# Laser_Charger.net
KiCad netlist of a schematic drawn in EAGLE
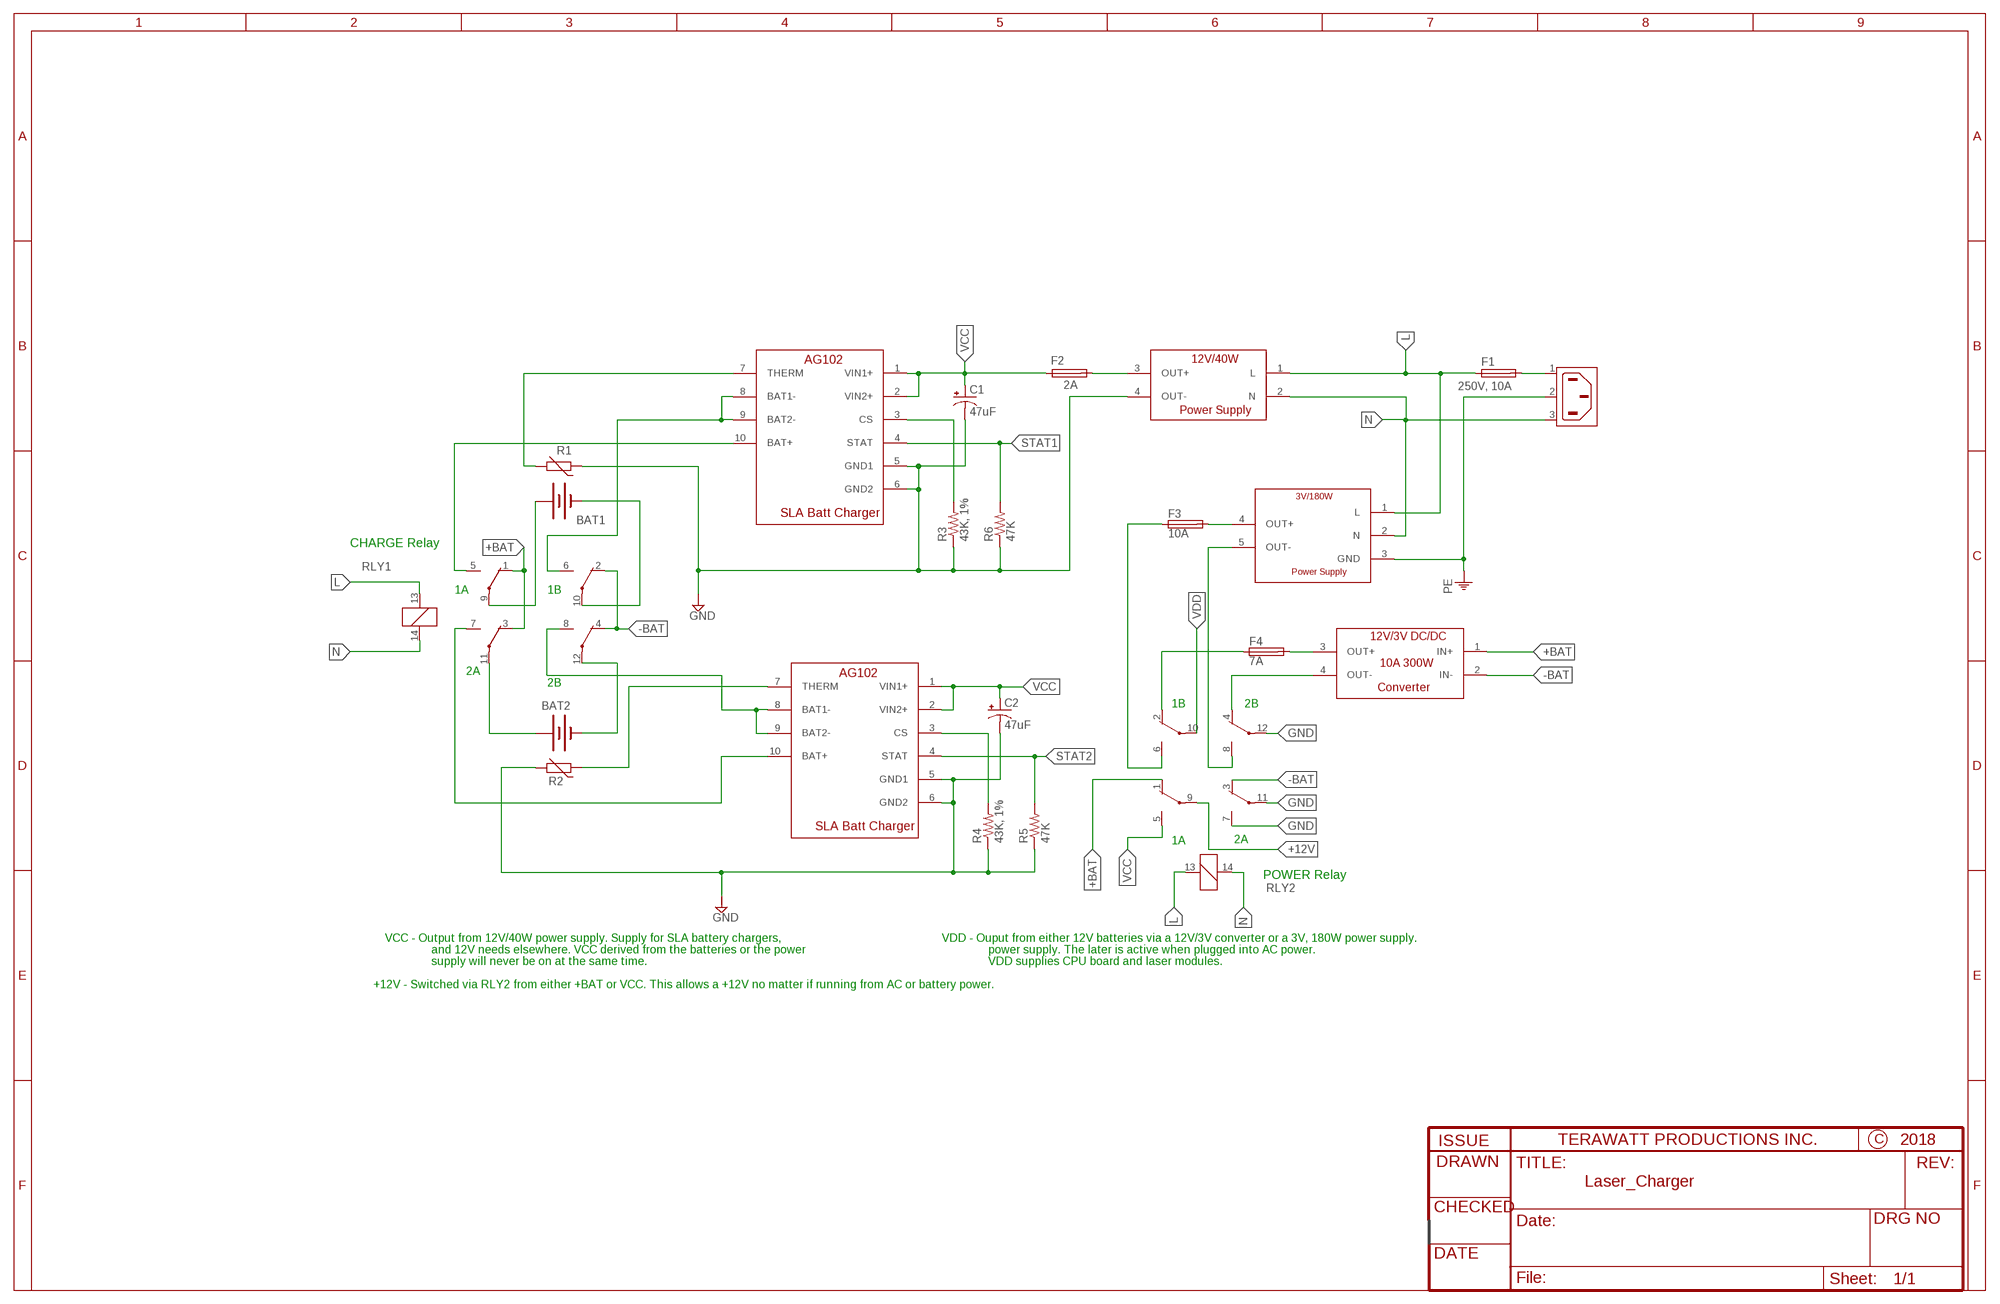
[diagram p0: schematic, sheet 1]

(export (version "E")
  (design (tool "Eeschema 10.0.6"))
  (components
    (comp (ref "BAT1")
      (value "BATTERY")
      (footprint "eagle-import:12V_BATT")
      (libsource (lib "eagle-import") (part "BATTERY"))
    )
    (comp (ref "BAT2")
      (value "BATTERY")
      (footprint "eagle-import:12V_BATT")
      (libsource (lib "eagle-import") (part "BATTERY"))
    )
    (comp (ref "C1")
      (value "47uF")
      (footprint "eagle-import:E5-10,5")
      (libsource (lib "eagle-import") (part "CPOL-USE5-10.5"))
    )
    (comp (ref "C2")
      (value "47uF")
      (footprint "eagle-import:E5-10,5")
      (libsource (lib "eagle-import") (part "CPOL-USE5-10.5"))
    )
    (comp (ref "CHG1")
      (value "AG102_SLA_CHARGER")
      (footprint "eagle-import:22-23-2101")
      (libsource (lib "eagle-import") (part "AG102_SLA_CHARGER"))
    )
    (comp (ref "CHG2")
      (value "AG102_SLA_CHARGER")
      (footprint "eagle-import:22-23-2101")
      (libsource (lib "eagle-import") (part "AG102_SLA_CHARGER"))
    )
    (comp (ref "F1")
      (value "250V, 10A")
      (footprint "eagle-import:SH22,5")
      (fields (field (name "MF") "SCHURTER") (field (name "MPN") "0031.8201"))
      (libsource (lib "eagle-import") (part "SH22,5"))
    )
    (comp (ref "F2")
      (value "2A")
      (footprint "eagle-import:SH22,5")
      (fields (field (name "MF") "SCHURTER") (field (name "MPN") "0031.8201"))
      (libsource (lib "eagle-import") (part "SH22,5"))
    )
    (comp (ref "F3")
      (value "10A")
      (footprint "eagle-import:SH22,5")
      (fields (field (name "MF") "SCHURTER") (field (name "MPN") "0031.8201"))
      (libsource (lib "eagle-import") (part "SH22,5"))
    )
    (comp (ref "F4")
      (value "7A")
      (footprint "eagle-import:SH22,5")
      (fields (field (name "MF") "SCHURTER") (field (name "MPN") "0031.8201"))
      (libsource (lib "eagle-import") (part "SH22,5"))
    )
    (comp (ref "P1")
      (value "12V/3V_DC/DC_CONVERTER")
      (footprint "eagle-import:12V_3V_DC_DC_CONVERTER")
      (libsource (lib "eagle-import") (part "12V/3V_DC/DC_CONVERTER"))
    )
    (comp (ref "PS1")
      (value "12V/40W_POWER_SUPPLY")
      (footprint "eagle-import:12V_40W_POWER_SUPPLY")
      (libsource (lib "eagle-import") (part "12V/40W_POWER_SUPPLY"))
    )
    (comp (ref "PS2")
      (value "3V/180W_POWER_SUPPLY")
      (footprint "eagle-import:3V_180W_POWER_SUPPLY")
      (libsource (lib "eagle-import") (part "3V/180W_POWER_SUPPLY"))
    )
    (comp (ref "R1")
      (value "THERMISTOR-2,5")
      (footprint "eagle-import:RS-2,5")
      (libsource (lib "eagle-import") (part "THERMISTOR-2,5"))
    )
    (comp (ref "R2")
      (value "THERMISTOR-2,5")
      (footprint "eagle-import:RS-2,5")
      (libsource (lib "eagle-import") (part "THERMISTOR-2,5"))
    )
    (comp (ref "R3")
      (value "43K, 1%")
      (footprint "eagle-import:R0805")
      (libsource (lib "eagle-import") (part "R-US_R0805"))
    )
    (comp (ref "R4")
      (value "43K, 1%")
      (footprint "eagle-import:R0805")
      (libsource (lib "eagle-import") (part "R-US_R0805"))
    )
    (comp (ref "R5")
      (value "47K")
      (footprint "eagle-import:R0805")
      (libsource (lib "eagle-import") (part "R-US_R0805"))
    )
    (comp (ref "R6")
      (value "47K")
      (footprint "eagle-import:R0805")
      (libsource (lib "eagle-import") (part "R-US_R0805"))
    )
    (comp (ref "RLY1")
      (value "4P4T_RELAYS")
      (footprint "eagle-import:22-23-2071-2")
      (libsource (lib "eagle-import") (part "4P4T_RELAYS"))
    )
    (comp (ref "RLY2")
      (value "4P4T_RELAYS")
      (footprint "eagle-import:22-23-2071-2")
      (libsource (lib "eagle-import") (part "4P4T_RELAYS"))
    )
    (comp (ref "X1")
      (value "6ESRM-P")
      (footprint "eagle-import:6ESRM-P")
      (fields (field (name "MF") "TYCO ELECTRONICS"))
      (libsource (lib "eagle-import") (part "6ESRM-P"))
    )
  )
  (nets
    (net (code "1") (name "+12V") (class "Default")
      (node (ref "RLY2") (pin "9") (pinfunction "P_9") (pintype "passive"))
    )
    (net (code "2") (name "+BAT") (class "Default")
      (node (ref "P1") (pin "1") (pinfunction "IN+_1") (pintype "bidirectional"))
      (node (ref "RLY1") (pin "1") (pinfunction "O_1") (pintype "passive"))
      (node (ref "RLY1") (pin "3") (pinfunction "O_3") (pintype "passive"))
      (node (ref "RLY2") (pin "1") (pinfunction "O_1") (pintype "passive"))
    )
    (net (code "3") (name "-BAT") (class "Default")
      (node (ref "P1") (pin "2") (pinfunction "IN-_2") (pintype "bidirectional"))
      (node (ref "RLY1") (pin "2") (pinfunction "O_2") (pintype "passive"))
      (node (ref "RLY1") (pin "4") (pinfunction "O_4") (pintype "passive"))
      (node (ref "RLY2") (pin "3") (pinfunction "O_3") (pintype "passive"))
    )
    (net (code "4") (name "GND") (class "Default")
      (node (ref "C1") (pin "-") (pinfunction "-_-") (pintype "passive"))
      (node (ref "C2") (pin "-") (pinfunction "-_-") (pintype "passive"))
      (node (ref "CHG1") (pin "5") (pinfunction "GND1_5") (pintype "bidirectional"))
      (node (ref "CHG1") (pin "6") (pinfunction "GND2_6") (pintype "bidirectional"))
      (node (ref "CHG2") (pin "5") (pinfunction "GND1_5") (pintype "bidirectional"))
      (node (ref "CHG2") (pin "6") (pinfunction "GND2_6") (pintype "bidirectional"))
      (node (ref "PS1") (pin "4") (pinfunction "OUT-_4") (pintype "bidirectional"))
      (node (ref "R1") (pin "1") (pinfunction "1_1") (pintype "passive"))
      (node (ref "R2") (pin "2") (pinfunction "2_2") (pintype "passive"))
      (node (ref "R3") (pin "1") (pinfunction "1_1") (pintype "passive"))
      (node (ref "R4") (pin "1") (pinfunction "1_1") (pintype "passive"))
      (node (ref "R5") (pin "1") (pinfunction "1_1") (pintype "passive"))
      (node (ref "R6") (pin "1") (pinfunction "1_1") (pintype "passive"))
      (node (ref "RLY2") (pin "11") (pinfunction "P_11") (pintype "passive"))
      (node (ref "RLY2") (pin "12") (pinfunction "P_12") (pintype "passive"))
      (node (ref "RLY2") (pin "7") (pinfunction "S_7") (pintype "passive"))
    )
    (net (code "5") (name "L") (class "Default")
      (node (ref "F1") (pin "1") (pinfunction "1_1") (pintype "passive"))
      (node (ref "PS1") (pin "1") (pinfunction "L_1") (pintype "bidirectional"))
      (node (ref "PS2") (pin "1") (pinfunction "L_1") (pintype "bidirectional"))
      (node (ref "RLY1") (pin "13") (pinfunction "1_13") (pintype "passive"))
      (node (ref "RLY2") (pin "13") (pinfunction "1_13") (pintype "passive"))
    )
    (net (code "6") (name "N") (class "Default")
      (node (ref "PS1") (pin "2") (pinfunction "N_2") (pintype "bidirectional"))
      (node (ref "PS2") (pin "2") (pinfunction "N_2") (pintype "bidirectional"))
      (node (ref "RLY1") (pin "14") (pinfunction "2_14") (pintype "passive"))
      (node (ref "RLY2") (pin "14") (pinfunction "2_14") (pintype "passive"))
      (node (ref "X1") (pin "3") (pinfunction "AC2_3") (pintype "passive"))
    )
    (net (code "7") (name "Net-(BAT1-+)") (class "Default")
      (node (ref "BAT1") (pin "1") (pinfunction "+_1") (pintype "power_in"))
      (node (ref "RLY1") (pin "9") (pinfunction "P_9") (pintype "passive"))
    )
    (net (code "8") (name "Net-(BAT1--)") (class "Default")
      (node (ref "BAT1") (pin "2") (pinfunction "-_2") (pintype "power_in"))
      (node (ref "RLY1") (pin "10") (pinfunction "P_10") (pintype "passive"))
    )
    (net (code "9") (name "Net-(BAT2-+)") (class "Default")
      (node (ref "BAT2") (pin "1") (pinfunction "+_1") (pintype "power_in"))
      (node (ref "RLY1") (pin "11") (pinfunction "P_11") (pintype "passive"))
    )
    (net (code "10") (name "Net-(BAT2--)") (class "Default")
      (node (ref "BAT2") (pin "2") (pinfunction "-_2") (pintype "power_in"))
      (node (ref "RLY1") (pin "12") (pinfunction "P_12") (pintype "passive"))
    )
    (net (code "11") (name "Net-(CHG1-BAT+)") (class "Default")
      (node (ref "CHG1") (pin "10") (pinfunction "BAT+_10") (pintype "bidirectional"))
      (node (ref "RLY1") (pin "5") (pinfunction "S_5") (pintype "passive"))
    )
    (net (code "12") (name "Net-(CHG1-BAT1-)") (class "Default")
      (node (ref "CHG1") (pin "8") (pinfunction "BAT1-_8") (pintype "bidirectional"))
      (node (ref "CHG1") (pin "9") (pinfunction "BAT2-_9") (pintype "bidirectional"))
      (node (ref "RLY1") (pin "6") (pinfunction "S_6") (pintype "passive"))
    )
    (net (code "13") (name "Net-(CHG1-CS)") (class "Default")
      (node (ref "CHG1") (pin "3") (pinfunction "CS_3") (pintype "bidirectional"))
      (node (ref "R3") (pin "2") (pinfunction "2_2") (pintype "passive"))
    )
    (net (code "14") (name "Net-(CHG1-THERM)") (class "Default")
      (node (ref "CHG1") (pin "7") (pinfunction "THERM_7") (pintype "bidirectional"))
      (node (ref "R1") (pin "2") (pinfunction "2_2") (pintype "passive"))
    )
    (net (code "15") (name "Net-(CHG2-BAT+)") (class "Default")
      (node (ref "CHG2") (pin "10") (pinfunction "BAT+_10") (pintype "bidirectional"))
      (node (ref "RLY1") (pin "7") (pinfunction "S_7") (pintype "passive"))
    )
    (net (code "16") (name "Net-(CHG2-BAT1-)") (class "Default")
      (node (ref "CHG2") (pin "8") (pinfunction "BAT1-_8") (pintype "bidirectional"))
      (node (ref "CHG2") (pin "9") (pinfunction "BAT2-_9") (pintype "bidirectional"))
      (node (ref "RLY1") (pin "8") (pinfunction "S_8") (pintype "passive"))
    )
    (net (code "17") (name "Net-(CHG2-CS)") (class "Default")
      (node (ref "CHG2") (pin "3") (pinfunction "CS_3") (pintype "bidirectional"))
      (node (ref "R4") (pin "2") (pinfunction "2_2") (pintype "passive"))
    )
    (net (code "18") (name "Net-(CHG2-THERM)") (class "Default")
      (node (ref "CHG2") (pin "7") (pinfunction "THERM_7") (pintype "bidirectional"))
      (node (ref "R2") (pin "1") (pinfunction "1_1") (pintype "passive"))
    )
    (net (code "19") (name "Net-(P1-OUT+)") (class "Default")
      (node (ref "F4") (pin "2") (pinfunction "2_2") (pintype "passive"))
      (node (ref "P1") (pin "3") (pinfunction "OUT+_3") (pintype "bidirectional"))
    )
    (net (code "20") (name "Net-(P1-OUT-)") (class "Default")
      (node (ref "P1") (pin "4") (pinfunction "OUT-_4") (pintype "bidirectional"))
      (node (ref "RLY2") (pin "4") (pinfunction "O_4") (pintype "passive"))
    )
    (net (code "21") (name "Net-(PS1-OUT+)") (class "Default")
      (node (ref "F2") (pin "2") (pinfunction "2_2") (pintype "passive"))
      (node (ref "PS1") (pin "3") (pinfunction "OUT+_3") (pintype "bidirectional"))
    )
    (net (code "22") (name "Net-(PS2-OUT+)") (class "Default")
      (node (ref "F3") (pin "2") (pinfunction "2_2") (pintype "passive"))
      (node (ref "PS2") (pin "4") (pinfunction "OUT+_4") (pintype "bidirectional"))
    )
    (net (code "23") (name "Net-(PS2-OUT-)") (class "Default")
      (node (ref "PS2") (pin "5") (pinfunction "OUT-_5") (pintype "bidirectional"))
      (node (ref "RLY2") (pin "8") (pinfunction "S_8") (pintype "passive"))
    )
    (net (code "24") (name "Net-(RLY2B-O)") (class "Default")
      (node (ref "F4") (pin "1") (pinfunction "1_1") (pintype "passive"))
      (node (ref "RLY2") (pin "2") (pinfunction "O_2") (pintype "passive"))
    )
    (net (code "25") (name "Net-(RLY2B-S)") (class "Default")
      (node (ref "F3") (pin "1") (pinfunction "1_1") (pintype "passive"))
      (node (ref "RLY2") (pin "6") (pinfunction "S_6") (pintype "passive"))
    )
    (net (code "26") (name "Net-(X1-AC1)") (class "Default")
      (node (ref "F1") (pin "2") (pinfunction "2_2") (pintype "passive"))
      (node (ref "X1") (pin "1") (pinfunction "AC1_1") (pintype "passive"))
    )
    (net (code "27") (name "PE") (class "Default")
      (node (ref "PS2") (pin "3") (pinfunction "GND_3") (pintype "bidirectional"))
      (node (ref "X1") (pin "2") (pinfunction "SH_2") (pintype "passive"))
    )
    (net (code "28") (name "STAT1") (class "Default")
      (node (ref "CHG1") (pin "4") (pinfunction "STAT_4") (pintype "bidirectional"))
      (node (ref "R6") (pin "2") (pinfunction "2_2") (pintype "passive"))
    )
    (net (code "29") (name "STAT2") (class "Default")
      (node (ref "CHG2") (pin "4") (pinfunction "STAT_4") (pintype "bidirectional"))
      (node (ref "R5") (pin "2") (pinfunction "2_2") (pintype "passive"))
    )
    (net (code "30") (name "VCC") (class "Default")
      (node (ref "C1") (pin "+") (pinfunction "+_+") (pintype "passive"))
      (node (ref "C2") (pin "+") (pinfunction "+_+") (pintype "passive"))
      (node (ref "CHG1") (pin "1") (pinfunction "VIN1+_1") (pintype "bidirectional"))
      (node (ref "CHG1") (pin "2") (pinfunction "VIN2+_2") (pintype "bidirectional"))
      (node (ref "CHG2") (pin "1") (pinfunction "VIN1+_1") (pintype "bidirectional"))
      (node (ref "CHG2") (pin "2") (pinfunction "VIN2+_2") (pintype "bidirectional"))
      (node (ref "F2") (pin "1") (pinfunction "1_1") (pintype "passive"))
      (node (ref "RLY2") (pin "5") (pinfunction "S_5") (pintype "passive"))
    )
    (net (code "31") (name "VDD") (class "Default")
      (node (ref "RLY2") (pin "10") (pinfunction "P_10") (pintype "passive"))
    )
  )
)
